# gripper-rev3.net
KiCad netlist of a schematic drawn in EAGLE
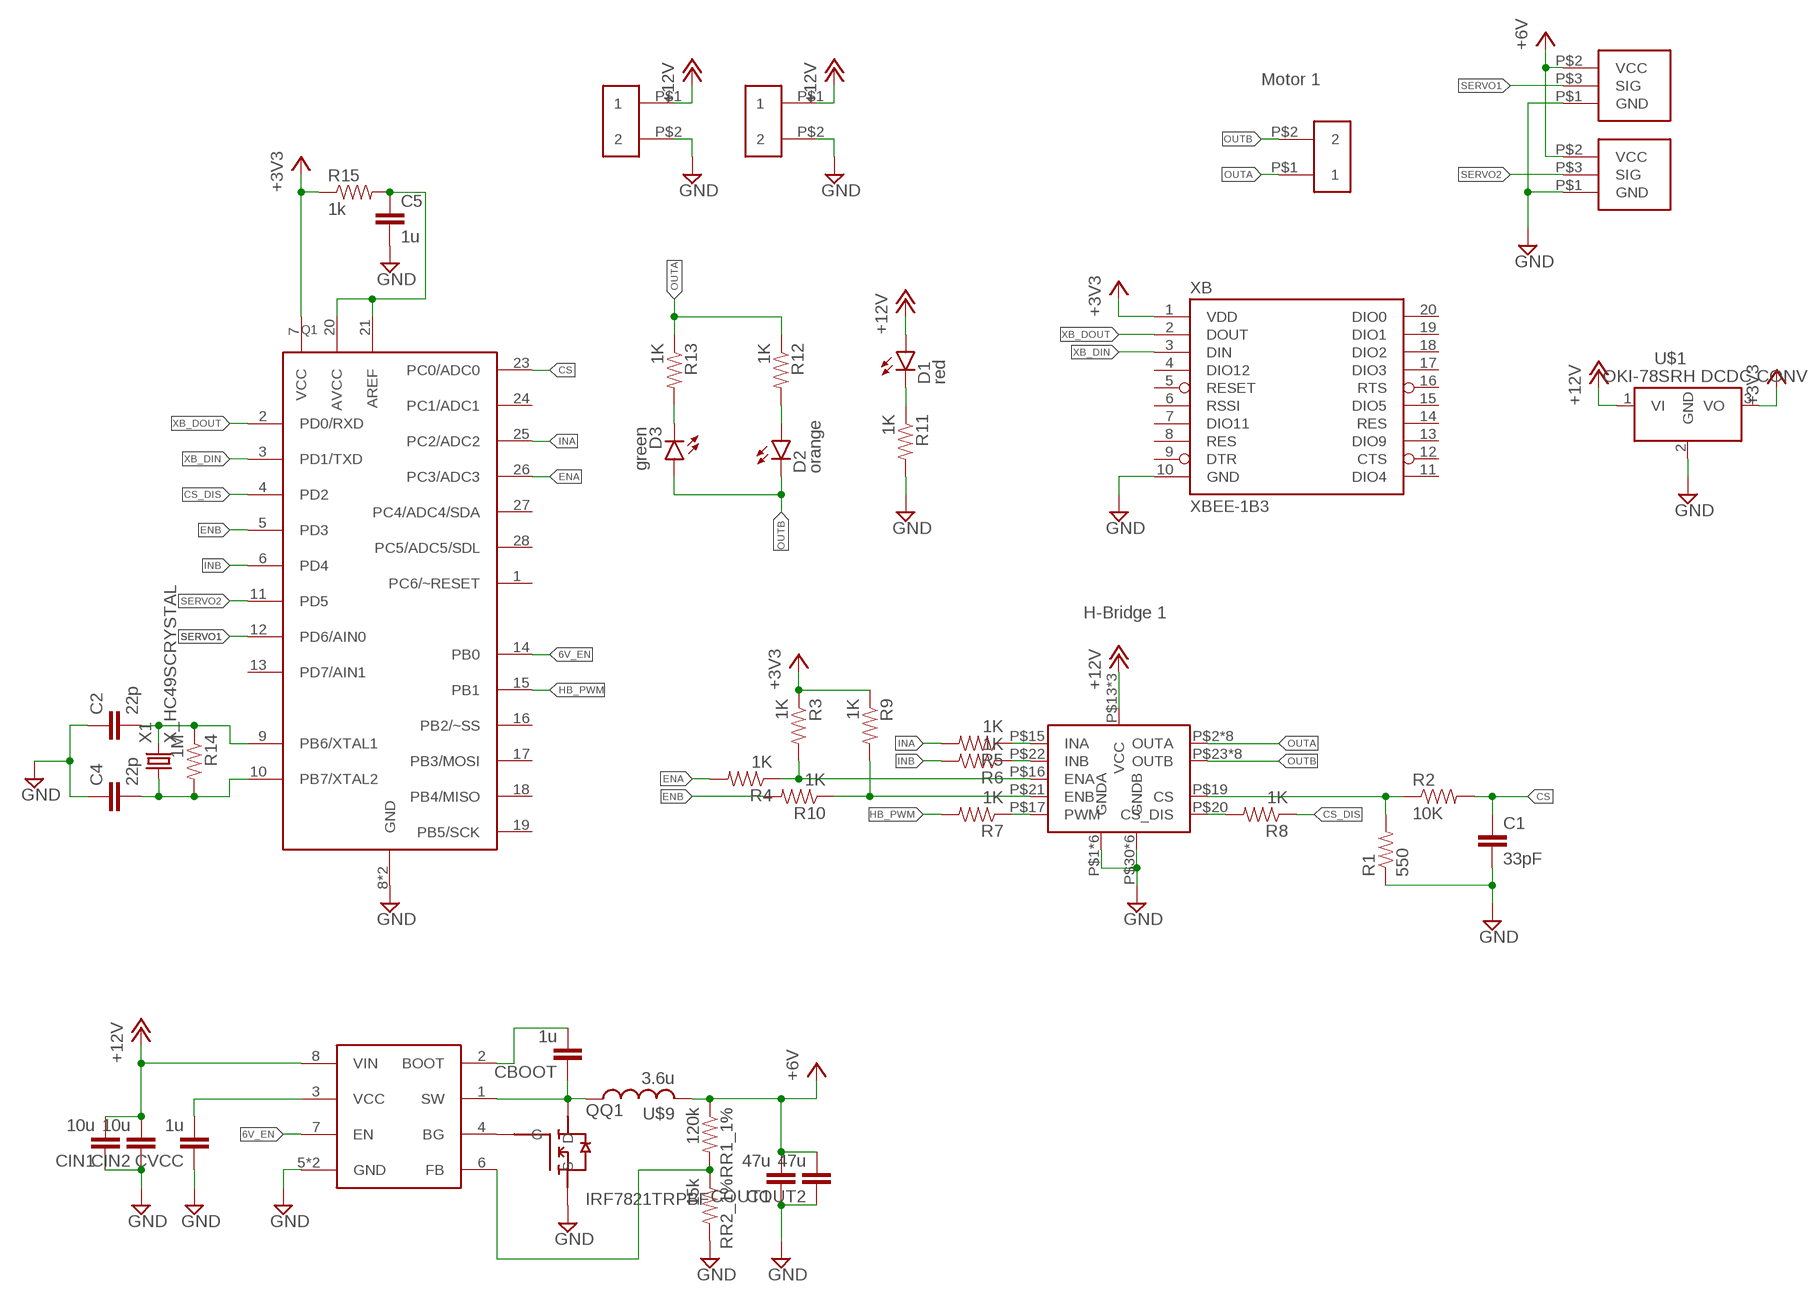
[diagram p0: schematic, sheet 1]

(export (version "E")
  (design (tool "Eeschema 10.0.6"))
  (components
    (comp (ref "C1")
      (value "33pF")
      (footprint "eagle-import:0603-CAP")
      (libsource (lib "eagle-import") (part "SparkFun-Passives_CAP0603-CAP"))
    )
    (comp (ref "C2")
      (value "22p")
      (footprint "eagle-import:0603-CAP")
      (libsource (lib "eagle-import") (part "SparkFun-Passives_CAP0603-CAP"))
    )
    (comp (ref "C4")
      (value "22p")
      (footprint "eagle-import:0603-CAP")
      (libsource (lib "eagle-import") (part "SparkFun-Passives_CAP0603-CAP"))
    )
    (comp (ref "C5")
      (value "1u")
      (footprint "eagle-import:0603-CAP")
      (libsource (lib "eagle-import") (part "SparkFun-Passives_CAP0603-CAP"))
    )
    (comp (ref "CBOOT")
      (value "1u")
      (footprint "eagle-import:0603-CAP")
      (libsource (lib "eagle-import") (part "SparkFun-Passives_CAP0603-CAP"))
    )
    (comp (ref "CIN1")
      (value "10u")
      (footprint "eagle-import:1206")
      (libsource (lib "eagle-import") (part "CAP1206"))
    )
    (comp (ref "CIN2")
      (value "10u")
      (footprint "eagle-import:1206")
      (libsource (lib "eagle-import") (part "CAP1206"))
    )
    (comp (ref "COUT1")
      (value "47u")
      (footprint "eagle-import:1206")
      (libsource (lib "eagle-import") (part "CAP1206"))
    )
    (comp (ref "COUT2")
      (value "47u")
      (footprint "eagle-import:1206")
      (libsource (lib "eagle-import") (part "CAP1206"))
    )
    (comp (ref "CVCC")
      (value "1u")
      (footprint "eagle-import:0603-CAP")
      (libsource (lib "eagle-import") (part "SparkFun-Passives_CAP0603-CAP"))
    )
    (comp (ref "D1")
      (value "red")
      (footprint "eagle-import:LED-0603")
      (libsource (lib "eagle-import") (part "LED0603"))
    )
    (comp (ref "D2")
      (value "orange")
      (footprint "eagle-import:LED-0603")
      (libsource (lib "eagle-import") (part "LED0603"))
    )
    (comp (ref "D3")
      (value "green")
      (footprint "eagle-import:LED-0603")
      (libsource (lib "eagle-import") (part "LED0603"))
    )
    (comp (ref "Q1")
      (value "Q_ATMEGA328P")
      (footprint "eagle-import:DIP28")
      (libsource (lib "eagle-import") (part "Q_ATMEGA328P"))
    )
    (comp (ref "QQ1")
      (value "IRF7821TRPBF")
      (footprint "eagle-import:SO-08")
      (libsource (lib "eagle-import") (part "IRF7821TRPBF"))
    )
    (comp (ref "R1")
      (value "550")
      (footprint "eagle-import:0603-RES")
      (libsource (lib "eagle-import") (part "RESISTOR0603"))
    )
    (comp (ref "R2")
      (value "10K")
      (footprint "eagle-import:0603-RES")
      (libsource (lib "eagle-import") (part "RESISTOR0603"))
    )
    (comp (ref "R3")
      (value "1K")
      (footprint "eagle-import:0603-RES")
      (libsource (lib "eagle-import") (part "RESISTOR0603"))
    )
    (comp (ref "R4")
      (value "1K")
      (footprint "eagle-import:0603-RES")
      (libsource (lib "eagle-import") (part "RESISTOR0603"))
    )
    (comp (ref "R5")
      (value "1K")
      (footprint "eagle-import:0603-RES")
      (libsource (lib "eagle-import") (part "RESISTOR0603"))
    )
    (comp (ref "R6")
      (value "1K")
      (footprint "eagle-import:0603-RES")
      (libsource (lib "eagle-import") (part "RESISTOR0603"))
    )
    (comp (ref "R7")
      (value "1K")
      (footprint "eagle-import:0603-RES")
      (libsource (lib "eagle-import") (part "RESISTOR0603"))
    )
    (comp (ref "R8")
      (value "1K")
      (footprint "eagle-import:0603-RES")
      (libsource (lib "eagle-import") (part "RESISTOR0603"))
    )
    (comp (ref "R9")
      (value "1K")
      (footprint "eagle-import:0603-RES")
      (libsource (lib "eagle-import") (part "RESISTOR0603"))
    )
    (comp (ref "R10")
      (value "1K")
      (footprint "eagle-import:0603-RES")
      (libsource (lib "eagle-import") (part "RESISTOR0603"))
    )
    (comp (ref "R11")
      (value "1K")
      (footprint "eagle-import:0603-RES")
      (libsource (lib "eagle-import") (part "RESISTOR0603"))
    )
    (comp (ref "R12")
      (value "1K")
      (footprint "eagle-import:0603-RES")
      (libsource (lib "eagle-import") (part "RESISTOR0603"))
    )
    (comp (ref "R13")
      (value "1K")
      (footprint "eagle-import:0603-RES")
      (libsource (lib "eagle-import") (part "RESISTOR0603"))
    )
    (comp (ref "R14")
      (value "1M")
      (footprint "eagle-import:0603-RES")
      (libsource (lib "eagle-import") (part "RESISTOR0603"))
    )
    (comp (ref "R15")
      (value "1k")
      (footprint "eagle-import:0603-RES")
      (libsource (lib "eagle-import") (part "RESISTOR0603"))
    )
    (comp (ref "RR1_1%")
      (value "120k")
      (footprint "eagle-import:0603-RES")
      (libsource (lib "eagle-import") (part "RESISTOR0603"))
    )
    (comp (ref "RR2_1%")
      (value "15k")
      (footprint "eagle-import:0603-RES")
      (libsource (lib "eagle-import") (part "RESISTOR0603"))
    )
    (comp (ref "RT7258")
      (value "RT7258GSP")
      (footprint "eagle-import:SOP08_W_EP")
      (libsource (lib "eagle-import") (part "RT7258GSP"))
    )
    (comp (ref "U$1")
      (value "Q_OKI-78SR")
      (footprint "eagle-import:OKI-78SR_HORIZ")
      (libsource (lib "eagle-import") (part "Q_OKI-78SR"))
    )
    (comp (ref "U$2")
      (value "SERVOHORIZ")
      (footprint "eagle-import:78208-103HLF")
      (libsource (lib "eagle-import") (part "SERVOHORIZ"))
    )
    (comp (ref "U$3")
      (value "SERVOHORIZ")
      (footprint "eagle-import:78208-103HLF")
      (libsource (lib "eagle-import") (part "SERVOHORIZ"))
    )
    (comp (ref "U$4")
      (value "VNH5XXX_HBRIDGEVNH5050A")
      (footprint "eagle-import:POWERSSO-36_TP")
      (libsource (lib "eagle-import") (part "VNH5XXX_HBRIDGEVNH5050A"))
    )
    (comp (ref "U$5")
      (value "M02SCREWTERM_HORIZ")
      (footprint "eagle-import:PC_1935161")
      (libsource (lib "eagle-import") (part "M02SCREWTERM_HORIZ"))
    )
    (comp (ref "U$6")
      (value "M02SCREWTERM_HORIZ")
      (footprint "eagle-import:PC_1935161")
      (libsource (lib "eagle-import") (part "M02SCREWTERM_HORIZ"))
    )
    (comp (ref "U$7")
      (value "M02SCREWTERM_VERT")
      (footprint "eagle-import:PC_1935310")
      (libsource (lib "eagle-import") (part "M02SCREWTERM_VERT"))
    )
    (comp (ref "U$9")
      (value "3.6u")
      (footprint "eagle-import:NR8040T3R6N")
      (libsource (lib "eagle-import") (part "NR8040T3R6N"))
    )
    (comp (ref "X1")
      (value "X_HC49SCRYSTAL")
      (footprint "eagle-import:HC-49")
      (libsource (lib "eagle-import") (part "X_HC49SCRYSTAL"))
    )
    (comp (ref "XB")
      (value "XBEE-1B3")
      (footprint "eagle-import:XBEE-SMD")
      (libsource (lib "eagle-import") (part "XBEE-1B3"))
    )
  )
  (nets
    (net (code "1") (name "+3V3") (class "Default")
      (node (ref "Q1") (pin "7") (pinfunction "VCC_7") (pintype "bidirectional"))
      (node (ref "R15") (pin "1") (pinfunction "1_1") (pintype "passive"))
      (node (ref "R3") (pin "1") (pinfunction "1_1") (pintype "passive"))
      (node (ref "R9") (pin "1") (pinfunction "1_1") (pintype "passive"))
      (node (ref "U$1") (pin "3") (pinfunction "VO_3") (pintype "bidirectional"))
      (node (ref "XB") (pin "1") (pinfunction "VDD_1") (pintype "power_in"))
    )
    (net (code "2") (name "+6V") (class "Default")
      (node (ref "COUT1") (pin "2") (pinfunction "2_2") (pintype "passive"))
      (node (ref "COUT2") (pin "2") (pinfunction "2_2") (pintype "passive"))
      (node (ref "RR1_1%") (pin "1") (pinfunction "1_1") (pintype "passive"))
      (node (ref "U$2") (pin "P$2") (pinfunction "VCC_P$2") (pintype "bidirectional"))
      (node (ref "U$3") (pin "P$2") (pinfunction "VCC_P$2") (pintype "bidirectional"))
      (node (ref "U$9") (pin "P$2") (pinfunction "2_P$2") (pintype "passive"))
    )
    (net (code "3") (name "+12V") (class "Default")
      (node (ref "CIN1") (pin "2") (pinfunction "2_2") (pintype "passive"))
      (node (ref "CIN2") (pin "2") (pinfunction "2_2") (pintype "passive"))
      (node (ref "D1") (pin "A") (pinfunction "A_A") (pintype "passive"))
      (node (ref "RT7258") (pin "8") (pinfunction "VIN_8") (pintype "bidirectional"))
      (node (ref "U$1") (pin "1") (pinfunction "VI_1") (pintype "bidirectional"))
      (node (ref "U$4") (pin "P$13") (pinfunction "VCC_P$13") (pintype "bidirectional"))
      (node (ref "U$4") (pin "P$24") (pinfunction "VCC_P$24") (pintype "bidirectional"))
      (node (ref "U$4") (pin "SLUG1") (pinfunction "VCC_SLUG1") (pintype "bidirectional"))
      (node (ref "U$5") (pin "P$1") (pinfunction "1_P$1") (pintype "power_in"))
      (node (ref "U$6") (pin "P$1") (pinfunction "1_P$1") (pintype "power_in"))
    )
    (net (code "4") (name "6V_EN") (class "Default")
      (node (ref "Q1") (pin "14") (pinfunction "PB0_14") (pintype "bidirectional"))
      (node (ref "RT7258") (pin "7") (pinfunction "EN_7") (pintype "bidirectional"))
    )
    (net (code "5") (name "CS") (class "Default")
      (node (ref "C1") (pin "1") (pinfunction "1_1") (pintype "passive"))
      (node (ref "Q1") (pin "23") (pinfunction "PC0/ADC0_23") (pintype "bidirectional"))
      (node (ref "R2") (pin "2") (pinfunction "2_2") (pintype "passive"))
    )
    (net (code "6") (name "CS_DIS") (class "Default")
      (node (ref "Q1") (pin "4") (pinfunction "PD2_4") (pintype "bidirectional"))
      (node (ref "R8") (pin "1") (pinfunction "1_1") (pintype "passive"))
    )
    (net (code "7") (name "ENA") (class "Default")
      (node (ref "Q1") (pin "26") (pinfunction "PC3/ADC3_26") (pintype "bidirectional"))
      (node (ref "R4") (pin "2") (pinfunction "2_2") (pintype "passive"))
    )
    (net (code "8") (name "ENB") (class "Default")
      (node (ref "Q1") (pin "5") (pinfunction "PD3_5") (pintype "bidirectional"))
      (node (ref "R10") (pin "2") (pinfunction "2_2") (pintype "passive"))
    )
    (net (code "9") (name "GND") (class "Default")
      (node (ref "C1") (pin "2") (pinfunction "2_2") (pintype "passive"))
      (node (ref "C2") (pin "1") (pinfunction "1_1") (pintype "passive"))
      (node (ref "C4") (pin "1") (pinfunction "1_1") (pintype "passive"))
      (node (ref "C5") (pin "2") (pinfunction "2_2") (pintype "passive"))
      (node (ref "CIN1") (pin "1") (pinfunction "1_1") (pintype "passive"))
      (node (ref "CIN2") (pin "1") (pinfunction "1_1") (pintype "passive"))
      (node (ref "COUT1") (pin "1") (pinfunction "1_1") (pintype "passive"))
      (node (ref "COUT2") (pin "1") (pinfunction "1_1") (pintype "passive"))
      (node (ref "CVCC") (pin "1") (pinfunction "1_1") (pintype "passive"))
      (node (ref "Q1") (pin "22") (pinfunction "GND_22") (pintype "bidirectional"))
      (node (ref "Q1") (pin "8") (pinfunction "GND_8") (pintype "bidirectional"))
      (node (ref "QQ1") (pin "1") (pinfunction "S_1") (pintype "bidirectional"))
      (node (ref "QQ1") (pin "2") (pinfunction "S_2") (pintype "bidirectional"))
      (node (ref "QQ1") (pin "3") (pinfunction "S_3") (pintype "bidirectional"))
      (node (ref "R1") (pin "1") (pinfunction "1_1") (pintype "passive"))
      (node (ref "R11") (pin "2") (pinfunction "2_2") (pintype "passive"))
      (node (ref "RR2_1%") (pin "2") (pinfunction "2_2") (pintype "passive"))
      (node (ref "RT7258") (pin "5") (pinfunction "GND_5") (pintype "bidirectional"))
      (node (ref "RT7258") (pin "EP") (pinfunction "GND_EP") (pintype "bidirectional"))
      (node (ref "U$1") (pin "2") (pinfunction "GND_2") (pintype "bidirectional"))
      (node (ref "U$2") (pin "P$1") (pinfunction "GND_P$1") (pintype "bidirectional"))
      (node (ref "U$3") (pin "P$1") (pinfunction "GND_P$1") (pintype "bidirectional"))
      (node (ref "U$4") (pin "P$1") (pinfunction "GNDA_P$1") (pintype "bidirectional"))
      (node (ref "U$4") (pin "P$3") (pinfunction "GNDA_P$3") (pintype "bidirectional"))
      (node (ref "U$4") (pin "P$30") (pinfunction "GNDB_P$30") (pintype "bidirectional"))
      (node (ref "U$4") (pin "P$31") (pinfunction "GNDB_P$31") (pintype "bidirectional"))
      (node (ref "U$4") (pin "P$32") (pinfunction "GNDB_P$32") (pintype "bidirectional"))
      (node (ref "U$4") (pin "P$33") (pinfunction "GNDB_P$33") (pintype "bidirectional"))
      (node (ref "U$4") (pin "P$34") (pinfunction "GNDB_P$34") (pintype "bidirectional"))
      (node (ref "U$4") (pin "P$36") (pinfunction "GNDB_P$36") (pintype "bidirectional"))
      (node (ref "U$4") (pin "P$4") (pinfunction "GNDA_P$4") (pintype "bidirectional"))
      (node (ref "U$4") (pin "P$5") (pinfunction "GNDA_P$5") (pintype "bidirectional"))
      (node (ref "U$4") (pin "P$6") (pinfunction "GNDA_P$6") (pintype "bidirectional"))
      (node (ref "U$4") (pin "P$7") (pinfunction "GNDA_P$7") (pintype "bidirectional"))
      (node (ref "U$5") (pin "P$2") (pinfunction "2_P$2") (pintype "power_in"))
      (node (ref "U$6") (pin "P$2") (pinfunction "2_P$2") (pintype "power_in"))
      (node (ref "XB") (pin "10") (pinfunction "GND_10") (pintype "power_in"))
    )
    (net (code "10") (name "HB_PWM") (class "Default")
      (node (ref "Q1") (pin "15") (pinfunction "PB1_15") (pintype "bidirectional"))
      (node (ref "R7") (pin "2") (pinfunction "2_2") (pintype "passive"))
    )
    (net (code "11") (name "INA") (class "Default")
      (node (ref "Q1") (pin "25") (pinfunction "PC2/ADC2_25") (pintype "bidirectional"))
      (node (ref "R5") (pin "2") (pinfunction "2_2") (pintype "passive"))
    )
    (net (code "12") (name "INB") (class "Default")
      (node (ref "Q1") (pin "6") (pinfunction "PD4_6") (pintype "bidirectional"))
      (node (ref "R6") (pin "2") (pinfunction "2_2") (pintype "passive"))
    )
    (net (code "13") (name "Net-(D1-PadC)") (class "Default")
      (node (ref "D1") (pin "C") (pinfunction "C_C") (pintype "passive"))
      (node (ref "R11") (pin "1") (pinfunction "1_1") (pintype "passive"))
    )
    (net (code "14") (name "Net-(D2-PadA)") (class "Default")
      (node (ref "D2") (pin "A") (pinfunction "A_A") (pintype "passive"))
      (node (ref "R12") (pin "2") (pinfunction "2_2") (pintype "passive"))
    )
    (net (code "15") (name "Net-(D3-PadC)") (class "Default")
      (node (ref "D3") (pin "C") (pinfunction "C_C") (pintype "passive"))
      (node (ref "R13") (pin "2") (pinfunction "2_2") (pintype "passive"))
    )
    (net (code "16") (name "Net-(Q1-AREF)") (class "Default")
      (node (ref "C5") (pin "1") (pinfunction "1_1") (pintype "passive"))
      (node (ref "Q1") (pin "20") (pinfunction "AVCC_20") (pintype "bidirectional"))
      (node (ref "Q1") (pin "21") (pinfunction "AREF_21") (pintype "bidirectional"))
      (node (ref "R15") (pin "2") (pinfunction "2_2") (pintype "passive"))
    )
    (net (code "17") (name "Net-(Q1-PB6{slash}XTAL1)") (class "Default")
      (node (ref "C2") (pin "2") (pinfunction "2_2") (pintype "passive"))
      (node (ref "Q1") (pin "9") (pinfunction "PB6/XTAL1_9") (pintype "bidirectional"))
      (node (ref "R14") (pin "1") (pinfunction "1_1") (pintype "passive"))
      (node (ref "X1") (pin "P$2") (pinfunction "2_P$2") (pintype "passive"))
    )
    (net (code "18") (name "Net-(Q1-PB7{slash}XTAL2)") (class "Default")
      (node (ref "C4") (pin "2") (pinfunction "2_2") (pintype "passive"))
      (node (ref "Q1") (pin "10") (pinfunction "PB7/XTAL2_10") (pintype "bidirectional"))
      (node (ref "R14") (pin "2") (pinfunction "2_2") (pintype "passive"))
      (node (ref "X1") (pin "P$1") (pinfunction "1_P$1") (pintype "passive"))
    )
    (net (code "19") (name "Net-(QQ1-G)") (class "Default")
      (node (ref "QQ1") (pin "4") (pinfunction "G_4") (pintype "bidirectional"))
      (node (ref "RT7258") (pin "4") (pinfunction "BG_4") (pintype "bidirectional"))
    )
    (net (code "20") (name "Net-(RT7258-BOOT)") (class "Default")
      (node (ref "CBOOT") (pin "2") (pinfunction "2_2") (pintype "passive"))
      (node (ref "RT7258") (pin "2") (pinfunction "BOOT_2") (pintype "bidirectional"))
    )
    (net (code "21") (name "Net-(RT7258-FB)") (class "Default")
      (node (ref "RR1_1%") (pin "2") (pinfunction "2_2") (pintype "passive"))
      (node (ref "RR2_1%") (pin "1") (pinfunction "1_1") (pintype "passive"))
      (node (ref "RT7258") (pin "6") (pinfunction "FB_6") (pintype "bidirectional"))
    )
    (net (code "22") (name "Net-(RT7258-SW)") (class "Default")
      (node (ref "CBOOT") (pin "1") (pinfunction "1_1") (pintype "passive"))
      (node (ref "QQ1") (pin "5") (pinfunction "D_5") (pintype "bidirectional"))
      (node (ref "QQ1") (pin "6") (pinfunction "D_6") (pintype "bidirectional"))
      (node (ref "QQ1") (pin "7") (pinfunction "D_7") (pintype "bidirectional"))
      (node (ref "QQ1") (pin "8") (pinfunction "D_8") (pintype "bidirectional"))
      (node (ref "RT7258") (pin "1") (pinfunction "SW_1") (pintype "bidirectional"))
      (node (ref "U$9") (pin "P$1") (pinfunction "1_P$1") (pintype "passive"))
    )
    (net (code "23") (name "Net-(RT7258-VCC)") (class "Default")
      (node (ref "CVCC") (pin "2") (pinfunction "2_2") (pintype "passive"))
      (node (ref "RT7258") (pin "3") (pinfunction "VCC_3") (pintype "bidirectional"))
    )
    (net (code "24") (name "Net-(U$4-CS)") (class "Default")
      (node (ref "R1") (pin "2") (pinfunction "2_2") (pintype "passive"))
      (node (ref "R2") (pin "1") (pinfunction "1_1") (pintype "passive"))
      (node (ref "U$4") (pin "P$19") (pinfunction "CS_P$19") (pintype "bidirectional"))
    )
    (net (code "25") (name "Net-(U$4-CS_DIS)") (class "Default")
      (node (ref "R8") (pin "2") (pinfunction "2_2") (pintype "passive"))
      (node (ref "U$4") (pin "P$20") (pinfunction "CS_DIS_P$20") (pintype "bidirectional"))
    )
    (net (code "26") (name "Net-(U$4-ENA)") (class "Default")
      (node (ref "R3") (pin "2") (pinfunction "2_2") (pintype "passive"))
      (node (ref "R4") (pin "1") (pinfunction "1_1") (pintype "passive"))
      (node (ref "U$4") (pin "P$16") (pinfunction "ENA_P$16") (pintype "bidirectional"))
    )
    (net (code "27") (name "Net-(U$4-ENB)") (class "Default")
      (node (ref "R10") (pin "1") (pinfunction "1_1") (pintype "passive"))
      (node (ref "R9") (pin "2") (pinfunction "2_2") (pintype "passive"))
      (node (ref "U$4") (pin "P$21") (pinfunction "ENB_P$21") (pintype "bidirectional"))
    )
    (net (code "28") (name "Net-(U$4-INA)") (class "Default")
      (node (ref "R5") (pin "1") (pinfunction "1_1") (pintype "passive"))
      (node (ref "U$4") (pin "P$15") (pinfunction "INA_P$15") (pintype "bidirectional"))
    )
    (net (code "29") (name "Net-(U$4-INB)") (class "Default")
      (node (ref "R6") (pin "1") (pinfunction "1_1") (pintype "passive"))
      (node (ref "U$4") (pin "P$22") (pinfunction "INB_P$22") (pintype "bidirectional"))
    )
    (net (code "30") (name "Net-(U$4-PWM)") (class "Default")
      (node (ref "R7") (pin "1") (pinfunction "1_1") (pintype "passive"))
      (node (ref "U$4") (pin "P$17") (pinfunction "PWM_P$17") (pintype "bidirectional"))
    )
    (net (code "31") (name "OUTA") (class "Default")
      (node (ref "R12") (pin "1") (pinfunction "1_1") (pintype "passive"))
      (node (ref "R13") (pin "1") (pinfunction "1_1") (pintype "passive"))
      (node (ref "U$4") (pin "P$10") (pinfunction "OUTA_P$10") (pintype "bidirectional"))
      (node (ref "U$4") (pin "P$11") (pinfunction "OUTA_P$11") (pintype "bidirectional"))
      (node (ref "U$4") (pin "P$12") (pinfunction "OUTA_P$12") (pintype "bidirectional"))
      (node (ref "U$4") (pin "P$14") (pinfunction "OUTA_P$14") (pintype "bidirectional"))
      (node (ref "U$4") (pin "P$2") (pinfunction "OUTA_P$2") (pintype "bidirectional"))
      (node (ref "U$4") (pin "P$8") (pinfunction "OUTA_P$8") (pintype "bidirectional"))
      (node (ref "U$4") (pin "P$9") (pinfunction "OUTA_P$9") (pintype "bidirectional"))
      (node (ref "U$4") (pin "SLUG2") (pinfunction "OUTA_SLUG2") (pintype "bidirectional"))
      (node (ref "U$7") (pin "P$1") (pinfunction "1_P$1") (pintype "power_in"))
    )
    (net (code "32") (name "OUTB") (class "Default")
      (node (ref "D2") (pin "C") (pinfunction "C_C") (pintype "passive"))
      (node (ref "D3") (pin "A") (pinfunction "A_A") (pintype "passive"))
      (node (ref "U$4") (pin "P$23") (pinfunction "OUTB_P$23") (pintype "bidirectional"))
      (node (ref "U$4") (pin "P$25") (pinfunction "OUTB_P$25") (pintype "bidirectional"))
      (node (ref "U$4") (pin "P$26") (pinfunction "OUTB_P$26") (pintype "bidirectional"))
      (node (ref "U$4") (pin "P$27") (pinfunction "OUTB_P$27") (pintype "bidirectional"))
      (node (ref "U$4") (pin "P$28") (pinfunction "OUTB_P$28") (pintype "bidirectional"))
      (node (ref "U$4") (pin "P$29") (pinfunction "OUTB_P$29") (pintype "bidirectional"))
      (node (ref "U$4") (pin "P$35") (pinfunction "OUTB_P$35") (pintype "bidirectional"))
      (node (ref "U$4") (pin "SLUG3") (pinfunction "OUTB_SLUG3") (pintype "bidirectional"))
      (node (ref "U$7") (pin "P$2") (pinfunction "2_P$2") (pintype "power_in"))
    )
    (net (code "33") (name "SERVO1") (class "Default")
      (node (ref "Q1") (pin "12") (pinfunction "PD6/AIN0_12") (pintype "bidirectional"))
      (node (ref "U$2") (pin "P$3") (pinfunction "SIG_P$3") (pintype "bidirectional"))
    )
    (net (code "34") (name "SERVO2") (class "Default")
      (node (ref "Q1") (pin "11") (pinfunction "PD5_11") (pintype "bidirectional"))
      (node (ref "U$3") (pin "P$3") (pinfunction "SIG_P$3") (pintype "bidirectional"))
    )
    (net (code "35") (name "XB_DIN") (class "Default")
      (node (ref "Q1") (pin "3") (pinfunction "PD1/TXD_3") (pintype "bidirectional"))
      (node (ref "XB") (pin "3") (pinfunction "DIN_3") (pintype "input"))
    )
    (net (code "36") (name "XB_DOUT") (class "Default")
      (node (ref "Q1") (pin "2") (pinfunction "PD0/RXD_2") (pintype "bidirectional"))
      (node (ref "XB") (pin "2") (pinfunction "DOUT_2") (pintype "output"))
    )
    (net (code "37") (name "unconnected-(Q1-PB2{slash}~{SS}-Pad16)") (class "Default")
      (node (ref "Q1") (pin "16") (pinfunction "PB2/~{SS}_16") (pintype "bidirectional"))
    )
    (net (code "38") (name "unconnected-(Q1-PB3{slash}MOSI-Pad17)") (class "Default")
      (node (ref "Q1") (pin "17") (pinfunction "PB3/MOSI_17") (pintype "bidirectional"))
    )
    (net (code "39") (name "unconnected-(Q1-PB4{slash}MISO-Pad18)") (class "Default")
      (node (ref "Q1") (pin "18") (pinfunction "PB4/MISO_18") (pintype "bidirectional"))
    )
    (net (code "40") (name "unconnected-(Q1-PB5{slash}SCK-Pad19)") (class "Default")
      (node (ref "Q1") (pin "19") (pinfunction "PB5/SCK_19") (pintype "bidirectional"))
    )
    (net (code "41") (name "unconnected-(Q1-PC1{slash}ADC1-Pad24)") (class "Default")
      (node (ref "Q1") (pin "24") (pinfunction "PC1/ADC1_24") (pintype "bidirectional"))
    )
    (net (code "42") (name "unconnected-(Q1-PC4{slash}ADC4{slash}SDA-Pad27)") (class "Default")
      (node (ref "Q1") (pin "27") (pinfunction "PC4/ADC4/SDA_27") (pintype "bidirectional"))
    )
    (net (code "43") (name "unconnected-(Q1-PC5{slash}ADC5{slash}SDL-Pad28)") (class "Default")
      (node (ref "Q1") (pin "28") (pinfunction "PC5/ADC5/SDL_28") (pintype "bidirectional"))
    )
    (net (code "44") (name "unconnected-(Q1-PC6{slash}~{RESET}-Pad1)") (class "Default")
      (node (ref "Q1") (pin "1") (pinfunction "PC6/~{RESET}_1") (pintype "bidirectional"))
    )
    (net (code "45") (name "unconnected-(Q1-PD7{slash}AIN1-Pad13)") (class "Default")
      (node (ref "Q1") (pin "13") (pinfunction "PD7/AIN1_13") (pintype "bidirectional"))
    )
    (net (code "46") (name "unconnected-(XB-CTS-Pad12)") (class "Default")
      (node (ref "XB") (pin "12") (pinfunction "CTS_12") (pintype "output"))
    )
    (net (code "47") (name "unconnected-(XB-DIO0-Pad20)") (class "Default")
      (node (ref "XB") (pin "20") (pinfunction "DIO0_20") (pintype "bidirectional"))
    )
    (net (code "48") (name "unconnected-(XB-DIO1-Pad19)") (class "Default")
      (node (ref "XB") (pin "19") (pinfunction "DIO1_19") (pintype "bidirectional"))
    )
    (net (code "49") (name "unconnected-(XB-DIO2-Pad18)") (class "Default")
      (node (ref "XB") (pin "18") (pinfunction "DIO2_18") (pintype "bidirectional"))
    )
    (net (code "50") (name "unconnected-(XB-DIO3-Pad17)") (class "Default")
      (node (ref "XB") (pin "17") (pinfunction "DIO3_17") (pintype "bidirectional"))
    )
    (net (code "51") (name "unconnected-(XB-DIO4-Pad11)") (class "Default")
      (node (ref "XB") (pin "11") (pinfunction "DIO4_11") (pintype "bidirectional"))
    )
    (net (code "52") (name "unconnected-(XB-DIO5-Pad15)") (class "Default")
      (node (ref "XB") (pin "15") (pinfunction "DIO5_15") (pintype "bidirectional"))
    )
    (net (code "53") (name "unconnected-(XB-DIO9-Pad13)") (class "Default")
      (node (ref "XB") (pin "13") (pinfunction "DIO9_13") (pintype "bidirectional"))
    )
    (net (code "54") (name "unconnected-(XB-DIO11-Pad7)") (class "Default")
      (node (ref "XB") (pin "7") (pinfunction "DIO11_7") (pintype "bidirectional"))
    )
    (net (code "55") (name "unconnected-(XB-DIO12-Pad4)") (class "Default")
      (node (ref "XB") (pin "4") (pinfunction "DIO12_4") (pintype "bidirectional"))
    )
    (net (code "56") (name "unconnected-(XB-DTR-Pad9)") (class "Default")
      (node (ref "XB") (pin "9") (pinfunction "DTR_9") (pintype "bidirectional"))
    )
    (net (code "57") (name "unconnected-(XB-RES-Pad8)") (class "Default")
      (node (ref "XB") (pin "8") (pinfunction "RES_8") (pintype "bidirectional"))
    )
    (net (code "58") (name "unconnected-(XB-RES-Pad14)") (class "Default")
      (node (ref "XB") (pin "14") (pinfunction "RES_14") (pintype "bidirectional"))
    )
    (net (code "59") (name "unconnected-(XB-RESET-Pad5)") (class "Default")
      (node (ref "XB") (pin "5") (pinfunction "RESET_5") (pintype "input"))
    )
    (net (code "60") (name "unconnected-(XB-RSSI-Pad6)") (class "Default")
      (node (ref "XB") (pin "6") (pinfunction "RSSI_6") (pintype "bidirectional"))
    )
    (net (code "61") (name "unconnected-(XB-RTS-Pad16)") (class "Default")
      (node (ref "XB") (pin "16") (pinfunction "RTS_16") (pintype "input"))
    )
  )
)
